# littlebits_per.net
KiCad netlist of a schematic drawn in EAGLE
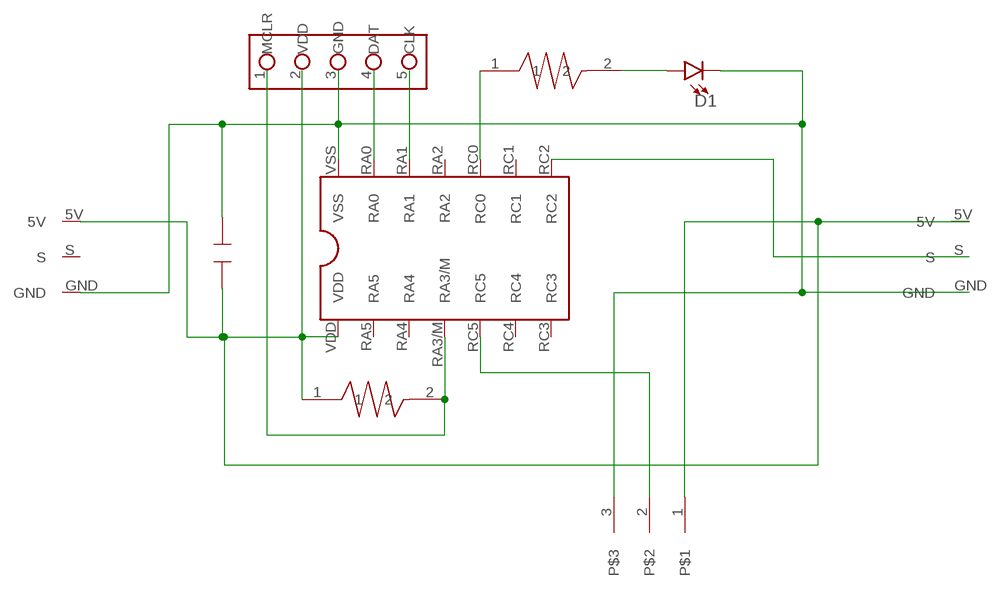
[diagram p0: schematic, sheet 1]

(export (version "E")
  (design (tool "Eeschema 10.0.6"))
  (components
    (comp (ref "D1")
      (value "LED-3MM-NO_SILK")
      (footprint "eagle-import:LED_3MM-NS")
      (libsource (lib "eagle-import") (part "LED-3MM-NO_SILK"))
    )
    (comp (ref "U$1")
      (value "ICSP")
      (footprint "eagle-import:ICSP")
      (libsource (lib "eagle-import") (part "ICSP"))
    )
    (comp (ref "U$2")
      (value "14PIN_DIP")
      (footprint "eagle-import:14PIN_DIP")
      (libsource (lib "eagle-import") (part "14PIN_DIP"))
    )
    (comp (ref "U$3")
      (value "RESISTOR")
      (footprint "eagle-import:RESISTOR")
      (libsource (lib "eagle-import") (part "RESISTOR"))
    )
    (comp (ref "U$4")
      (value "CAP-CERAMIC")
      (footprint "eagle-import:CAP-CERAMIC")
      (libsource (lib "eagle-import") (part "CAP-CERAMIC"))
    )
    (comp (ref "U$5")
      (value "LITTLEBITS_CON")
      (footprint "eagle-import:LITTLEBITS_CON")
      (libsource (lib "eagle-import") (part "LITTLEBITS_CON"))
    )
    (comp (ref "U$6")
      (value "LITTLEBITS_CON")
      (footprint "eagle-import:LITTLEBITS_CON")
      (libsource (lib "eagle-import") (part "LITTLEBITS_CON"))
    )
    (comp (ref "U$7")
      (value "CON3")
      (footprint "eagle-import:CON3")
      (libsource (lib "eagle-import") (part "CON3"))
    )
    (comp (ref "U$8")
      (value "RESISTOR")
      (footprint "eagle-import:RESISTOR")
      (libsource (lib "eagle-import") (part "RESISTOR"))
    )
  )
  (nets
    (net (code "1") (name "Net-(D1-C)") (class "Default")
      (node (ref "D1") (pin "K") (pinfunction "C_K") (pintype "passive"))
      (node (ref "U$1") (pin "3") (pinfunction "GND_3") (pintype "bidirectional"))
      (node (ref "U$2") (pin "VSS") (pinfunction "VSS_VSS") (pintype "bidirectional"))
      (node (ref "U$4") (pin "2") (pinfunction "2_2") (pintype "bidirectional"))
      (node (ref "U$5") (pin "GND") (pinfunction "GND_GND") (pintype "bidirectional"))
      (node (ref "U$6") (pin "GND") (pinfunction "GND_GND") (pintype "bidirectional"))
      (node (ref "U$7") (pin "3") (pinfunction "P$3_3") (pintype "bidirectional"))
    )
    (net (code "2") (name "Net-(D1-PadA)") (class "Default")
      (node (ref "D1") (pin "A") (pinfunction "A_A") (pintype "passive"))
      (node (ref "U$8") (pin "2") (pinfunction "2_2") (pintype "bidirectional"))
    )
    (net (code "3") (name "Net-(U$1-CLK)") (class "Default")
      (node (ref "U$1") (pin "5") (pinfunction "CLK_5") (pintype "bidirectional"))
      (node (ref "U$2") (pin "RA1") (pinfunction "RA1_RA1") (pintype "bidirectional"))
    )
    (net (code "4") (name "Net-(U$1-DAT)") (class "Default")
      (node (ref "U$1") (pin "4") (pinfunction "DAT_4") (pintype "bidirectional"))
      (node (ref "U$2") (pin "RA0") (pinfunction "RA0_RA0") (pintype "bidirectional"))
    )
    (net (code "5") (name "Net-(U$1-MCLR)") (class "Default")
      (node (ref "U$1") (pin "1") (pinfunction "MCLR_1") (pintype "bidirectional"))
      (node (ref "U$2") (pin "RA3/M") (pinfunction "RA3/M_RA3/M") (pintype "bidirectional"))
      (node (ref "U$3") (pin "2") (pinfunction "2_2") (pintype "bidirectional"))
    )
    (net (code "6") (name "Net-(U$1-VDD)") (class "Default")
      (node (ref "U$1") (pin "2") (pinfunction "VDD_2") (pintype "bidirectional"))
      (node (ref "U$2") (pin "VDD") (pinfunction "VDD_VDD") (pintype "bidirectional"))
      (node (ref "U$3") (pin "1") (pinfunction "1_1") (pintype "bidirectional"))
      (node (ref "U$4") (pin "1") (pinfunction "1_1") (pintype "bidirectional"))
      (node (ref "U$5") (pin "5V") (pinfunction "5V_5V") (pintype "bidirectional"))
      (node (ref "U$6") (pin "5V") (pinfunction "5V_5V") (pintype "bidirectional"))
      (node (ref "U$7") (pin "1") (pinfunction "P$1_1") (pintype "bidirectional"))
    )
    (net (code "7") (name "Net-(U$2-PadRC0)") (class "Default")
      (node (ref "U$2") (pin "RC0") (pinfunction "RC0_RC0") (pintype "bidirectional"))
      (node (ref "U$8") (pin "1") (pinfunction "1_1") (pintype "bidirectional"))
    )
    (net (code "8") (name "Net-(U$2-PadRC2)") (class "Default")
      (node (ref "U$2") (pin "RC2") (pinfunction "RC2_RC2") (pintype "bidirectional"))
      (node (ref "U$6") (pin "S") (pinfunction "S_S") (pintype "bidirectional"))
    )
    (net (code "9") (name "Net-(U$7-P$2)") (class "Default")
      (node (ref "U$2") (pin "RC5") (pinfunction "RC5_RC5") (pintype "bidirectional"))
      (node (ref "U$7") (pin "2") (pinfunction "P$2_2") (pintype "bidirectional"))
    )
    (net (code "10") (name "unconnected-(U$2-PadRA2)") (class "Default")
      (node (ref "U$2") (pin "RA2") (pinfunction "RA2_RA2") (pintype "bidirectional"))
    )
    (net (code "11") (name "unconnected-(U$2-PadRA4)") (class "Default")
      (node (ref "U$2") (pin "RA4") (pinfunction "RA4_RA4") (pintype "bidirectional"))
    )
    (net (code "12") (name "unconnected-(U$2-PadRA5)") (class "Default")
      (node (ref "U$2") (pin "RA5") (pinfunction "RA5_RA5") (pintype "bidirectional"))
    )
    (net (code "13") (name "unconnected-(U$2-PadRC1)") (class "Default")
      (node (ref "U$2") (pin "RC1") (pinfunction "RC1_RC1") (pintype "bidirectional"))
    )
    (net (code "14") (name "unconnected-(U$2-PadRC3)") (class "Default")
      (node (ref "U$2") (pin "RC3") (pinfunction "RC3_RC3") (pintype "bidirectional"))
    )
    (net (code "15") (name "unconnected-(U$2-PadRC4)") (class "Default")
      (node (ref "U$2") (pin "RC4") (pinfunction "RC4_RC4") (pintype "bidirectional"))
    )
    (net (code "16") (name "unconnected-(U$5-PadS)") (class "Default")
      (node (ref "U$5") (pin "S") (pinfunction "S_S") (pintype "bidirectional"))
    )
  )
)
